# Rear_Tail_Lights_FULL.net
KiCad netlist of a schematic drawn in Altium Designer
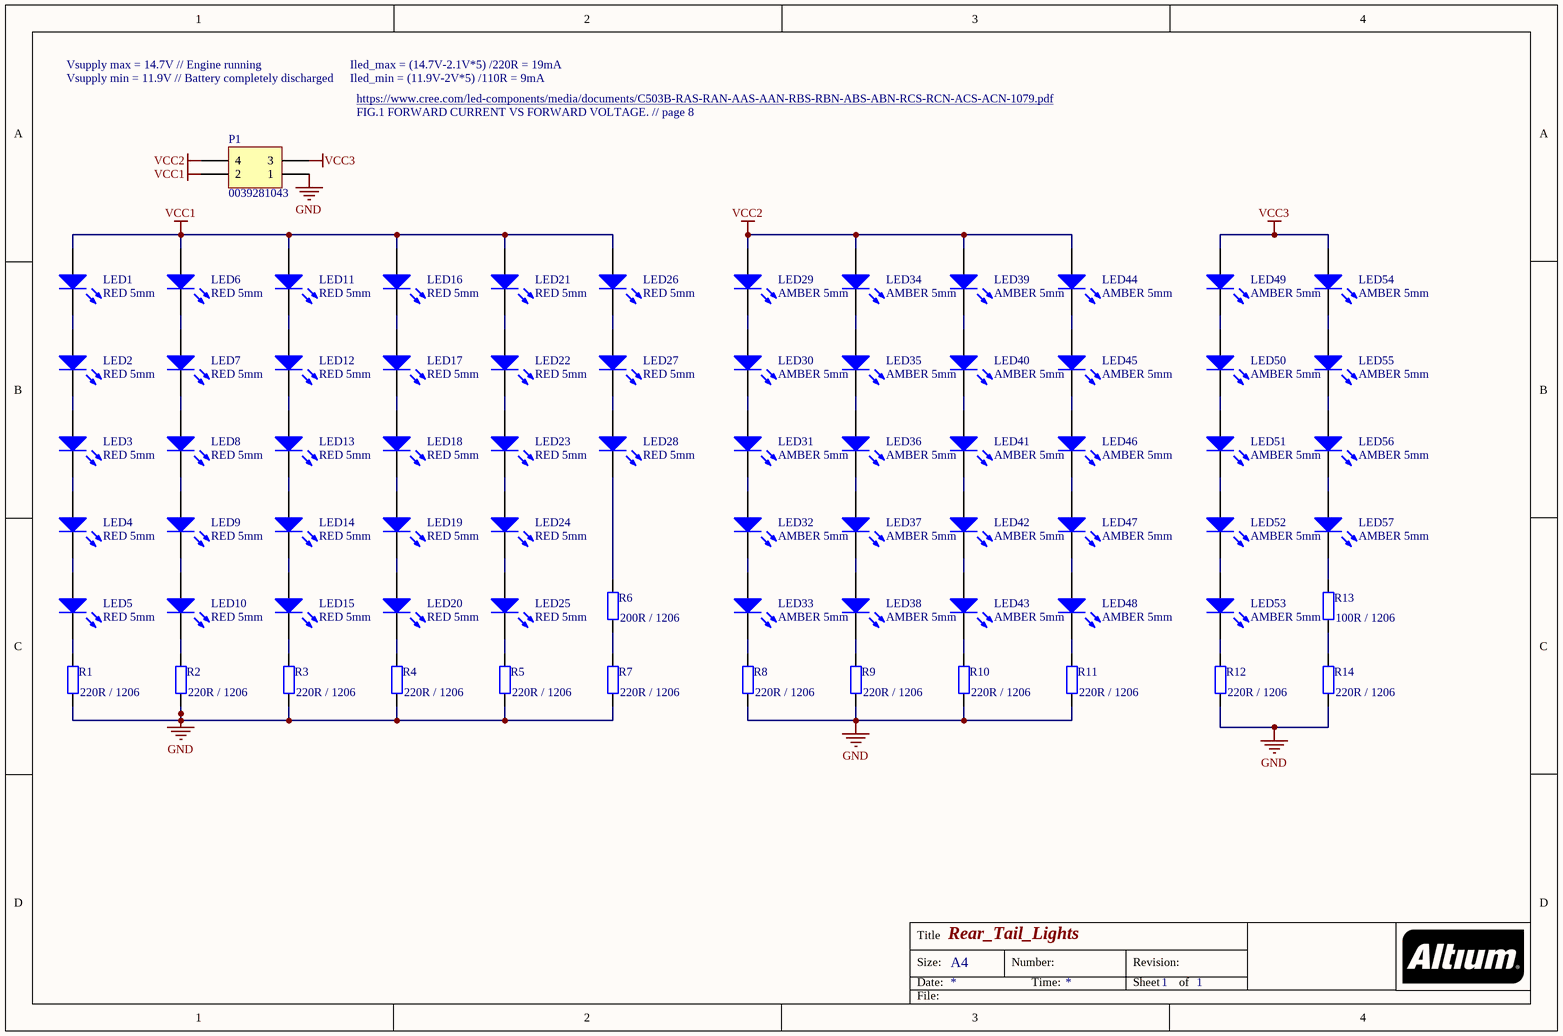
[diagram p0: Rear_Tail_Lights_FULL.SchDoc]

(export (version "E")
  (design (tool "Eeschema 10.0.6"))
  (components
    (comp (ref "LED1")
      (value "RED 5mm")
      (footprint "LED_5MM_RED_1C-2A")
      (description "LED GREEN CLEAR 0603 SMD")
      (fields (field (name "MANUFACTURER") "Lite-On Inc.") (field (name "PUBLISHER") "Altium Limited"))
      (libsource (lib "Miscellaneous Devices") (part "LED0"))
    )
    (comp (ref "LED2")
      (value "RED 5mm")
      (footprint "LED_5MM_RED_1C-2A")
      (description "LED GREEN CLEAR 0603 SMD")
      (fields (field (name "MANUFACTURER") "Lite-On Inc.") (field (name "PUBLISHER") "Altium Limited"))
      (libsource (lib "Miscellaneous Devices") (part "LED0"))
    )
    (comp (ref "LED3")
      (value "RED 5mm")
      (footprint "LED_5MM_RED_1C-2A")
      (description "LED GREEN CLEAR 0603 SMD")
      (fields (field (name "MANUFACTURER") "Lite-On Inc.") (field (name "PUBLISHER") "Altium Limited"))
      (libsource (lib "Miscellaneous Devices") (part "LED0"))
    )
    (comp (ref "LED4")
      (value "RED 5mm")
      (footprint "LED_5MM_RED_1C-2A")
      (description "LED GREEN CLEAR 0603 SMD")
      (fields (field (name "MANUFACTURER") "Lite-On Inc.") (field (name "PUBLISHER") "Altium Limited"))
      (libsource (lib "Miscellaneous Devices") (part "LED0"))
    )
    (comp (ref "LED5")
      (value "RED 5mm")
      (footprint "LED_5MM_RED_1C-2A")
      (description "LED GREEN CLEAR 0603 SMD")
      (fields (field (name "MANUFACTURER") "Lite-On Inc.") (field (name "PUBLISHER") "Altium Limited"))
      (libsource (lib "Miscellaneous Devices") (part "LED0"))
    )
    (comp (ref "LED6")
      (value "RED 5mm")
      (footprint "LED_5MM_RED_1C-2A")
      (description "LED GREEN CLEAR 0603 SMD")
      (fields (field (name "MANUFACTURER") "Lite-On Inc.") (field (name "PUBLISHER") "Altium Limited"))
      (libsource (lib "Miscellaneous Devices") (part "LED0"))
    )
    (comp (ref "LED7")
      (value "RED 5mm")
      (footprint "LED_5MM_RED_1C-2A")
      (description "LED GREEN CLEAR 0603 SMD")
      (fields (field (name "MANUFACTURER") "Lite-On Inc.") (field (name "PUBLISHER") "Altium Limited"))
      (libsource (lib "Miscellaneous Devices") (part "LED0"))
    )
    (comp (ref "LED8")
      (value "RED 5mm")
      (footprint "LED_5MM_RED_1C-2A")
      (description "LED GREEN CLEAR 0603 SMD")
      (fields (field (name "MANUFACTURER") "Lite-On Inc.") (field (name "PUBLISHER") "Altium Limited"))
      (libsource (lib "Miscellaneous Devices") (part "LED0"))
    )
    (comp (ref "LED9")
      (value "RED 5mm")
      (footprint "LED_5MM_RED_1C-2A")
      (description "LED GREEN CLEAR 0603 SMD")
      (fields (field (name "MANUFACTURER") "Lite-On Inc.") (field (name "PUBLISHER") "Altium Limited"))
      (libsource (lib "Miscellaneous Devices") (part "LED0"))
    )
    (comp (ref "LED10")
      (value "RED 5mm")
      (footprint "LED_5MM_RED_1C-2A")
      (description "LED GREEN CLEAR 0603 SMD")
      (fields (field (name "MANUFACTURER") "Lite-On Inc.") (field (name "PUBLISHER") "Altium Limited"))
      (libsource (lib "Miscellaneous Devices") (part "LED0"))
    )
    (comp (ref "LED11")
      (value "RED 5mm")
      (footprint "LED_5MM_RED_1C-2A")
      (description "LED GREEN CLEAR 0603 SMD")
      (fields (field (name "MANUFACTURER") "Lite-On Inc.") (field (name "PUBLISHER") "Altium Limited"))
      (libsource (lib "Miscellaneous Devices") (part "LED0"))
    )
    (comp (ref "LED12")
      (value "RED 5mm")
      (footprint "LED_5MM_RED_1C-2A")
      (description "LED GREEN CLEAR 0603 SMD")
      (fields (field (name "MANUFACTURER") "Lite-On Inc.") (field (name "PUBLISHER") "Altium Limited"))
      (libsource (lib "Miscellaneous Devices") (part "LED0"))
    )
    (comp (ref "LED13")
      (value "RED 5mm")
      (footprint "LED_5MM_RED_1C-2A")
      (description "LED GREEN CLEAR 0603 SMD")
      (fields (field (name "MANUFACTURER") "Lite-On Inc.") (field (name "PUBLISHER") "Altium Limited"))
      (libsource (lib "Miscellaneous Devices") (part "LED0"))
    )
    (comp (ref "LED14")
      (value "RED 5mm")
      (footprint "LED_5MM_RED_1C-2A")
      (description "LED GREEN CLEAR 0603 SMD")
      (fields (field (name "MANUFACTURER") "Lite-On Inc.") (field (name "PUBLISHER") "Altium Limited"))
      (libsource (lib "Miscellaneous Devices") (part "LED0"))
    )
    (comp (ref "LED15")
      (value "RED 5mm")
      (footprint "LED_5MM_RED_1C-2A")
      (description "LED GREEN CLEAR 0603 SMD")
      (fields (field (name "MANUFACTURER") "Lite-On Inc.") (field (name "PUBLISHER") "Altium Limited"))
      (libsource (lib "Miscellaneous Devices") (part "LED0"))
    )
    (comp (ref "LED16")
      (value "RED 5mm")
      (footprint "LED_5MM_RED_1C-2A")
      (description "LED GREEN CLEAR 0603 SMD")
      (fields (field (name "MANUFACTURER") "Lite-On Inc.") (field (name "PUBLISHER") "Altium Limited"))
      (libsource (lib "Miscellaneous Devices") (part "LED0"))
    )
    (comp (ref "LED17")
      (value "RED 5mm")
      (footprint "LED_5MM_RED_1C-2A")
      (description "LED GREEN CLEAR 0603 SMD")
      (fields (field (name "MANUFACTURER") "Lite-On Inc.") (field (name "PUBLISHER") "Altium Limited"))
      (libsource (lib "Miscellaneous Devices") (part "LED0"))
    )
    (comp (ref "LED18")
      (value "RED 5mm")
      (footprint "LED_5MM_RED_1C-2A")
      (description "LED GREEN CLEAR 0603 SMD")
      (fields (field (name "MANUFACTURER") "Lite-On Inc.") (field (name "PUBLISHER") "Altium Limited"))
      (libsource (lib "Miscellaneous Devices") (part "LED0"))
    )
    (comp (ref "LED19")
      (value "RED 5mm")
      (footprint "LED_5MM_RED_1C-2A")
      (description "LED GREEN CLEAR 0603 SMD")
      (fields (field (name "MANUFACTURER") "Lite-On Inc.") (field (name "PUBLISHER") "Altium Limited"))
      (libsource (lib "Miscellaneous Devices") (part "LED0"))
    )
    (comp (ref "LED20")
      (value "RED 5mm")
      (footprint "LED_5MM_RED_1C-2A")
      (description "LED GREEN CLEAR 0603 SMD")
      (fields (field (name "MANUFACTURER") "Lite-On Inc.") (field (name "PUBLISHER") "Altium Limited"))
      (libsource (lib "Miscellaneous Devices") (part "LED0"))
    )
    (comp (ref "LED21")
      (value "RED 5mm")
      (footprint "LED_5MM_RED_1C-2A")
      (description "LED GREEN CLEAR 0603 SMD")
      (fields (field (name "MANUFACTURER") "Lite-On Inc.") (field (name "PUBLISHER") "Altium Limited"))
      (libsource (lib "Miscellaneous Devices") (part "LED0"))
    )
    (comp (ref "LED22")
      (value "RED 5mm")
      (footprint "LED_5MM_RED_1C-2A")
      (description "LED GREEN CLEAR 0603 SMD")
      (fields (field (name "MANUFACTURER") "Lite-On Inc.") (field (name "PUBLISHER") "Altium Limited"))
      (libsource (lib "Miscellaneous Devices") (part "LED0"))
    )
    (comp (ref "LED23")
      (value "RED 5mm")
      (footprint "LED_5MM_RED_1C-2A")
      (description "LED GREEN CLEAR 0603 SMD")
      (fields (field (name "MANUFACTURER") "Lite-On Inc.") (field (name "PUBLISHER") "Altium Limited"))
      (libsource (lib "Miscellaneous Devices") (part "LED0"))
    )
    (comp (ref "LED24")
      (value "RED 5mm")
      (footprint "LED_5MM_RED_1C-2A")
      (description "LED GREEN CLEAR 0603 SMD")
      (fields (field (name "MANUFACTURER") "Lite-On Inc.") (field (name "PUBLISHER") "Altium Limited"))
      (libsource (lib "Miscellaneous Devices") (part "LED0"))
    )
    (comp (ref "LED25")
      (value "RED 5mm")
      (footprint "LED_5MM_RED_1C-2A")
      (description "LED GREEN CLEAR 0603 SMD")
      (fields (field (name "MANUFACTURER") "Lite-On Inc.") (field (name "PUBLISHER") "Altium Limited"))
      (libsource (lib "Miscellaneous Devices") (part "LED0"))
    )
    (comp (ref "LED26")
      (value "RED 5mm")
      (footprint "LED_5MM_RED_1C-2A")
      (description "LED GREEN CLEAR 0603 SMD")
      (fields (field (name "MANUFACTURER") "Lite-On Inc.") (field (name "PUBLISHER") "Altium Limited"))
      (libsource (lib "Miscellaneous Devices") (part "LED0"))
    )
    (comp (ref "LED27")
      (value "RED 5mm")
      (footprint "LED_5MM_RED_1C-2A")
      (description "LED GREEN CLEAR 0603 SMD")
      (fields (field (name "MANUFACTURER") "Lite-On Inc.") (field (name "PUBLISHER") "Altium Limited"))
      (libsource (lib "Miscellaneous Devices") (part "LED0"))
    )
    (comp (ref "LED28")
      (value "RED 5mm")
      (footprint "LED_5MM_RED_1C-2A")
      (description "LED GREEN CLEAR 0603 SMD")
      (fields (field (name "MANUFACTURER") "Lite-On Inc.") (field (name "PUBLISHER") "Altium Limited"))
      (libsource (lib "Miscellaneous Devices") (part "LED0"))
    )
    (comp (ref "LED29")
      (value "AMBER 5mm")
      (footprint "LED_5MM_YELLOW_1C-2A")
      (description "LED GREEN CLEAR 0603 SMD")
      (fields (field (name "MANUFACTURER") "Lite-On Inc.") (field (name "PUBLISHER") "Altium Limited"))
      (libsource (lib "Miscellaneous Devices") (part "LED0"))
    )
    (comp (ref "LED30")
      (value "AMBER 5mm")
      (footprint "LED_5MM_YELLOW_1C-2A")
      (description "LED GREEN CLEAR 0603 SMD")
      (fields (field (name "MANUFACTURER") "Lite-On Inc.") (field (name "PUBLISHER") "Altium Limited"))
      (libsource (lib "Miscellaneous Devices") (part "LED0"))
    )
    (comp (ref "LED31")
      (value "AMBER 5mm")
      (footprint "LED_5MM_YELLOW_1C-2A")
      (description "LED GREEN CLEAR 0603 SMD")
      (fields (field (name "MANUFACTURER") "Lite-On Inc.") (field (name "PUBLISHER") "Altium Limited"))
      (libsource (lib "Miscellaneous Devices") (part "LED0"))
    )
    (comp (ref "LED32")
      (value "AMBER 5mm")
      (footprint "LED_5MM_YELLOW_1C-2A")
      (description "LED GREEN CLEAR 0603 SMD")
      (fields (field (name "MANUFACTURER") "Lite-On Inc.") (field (name "PUBLISHER") "Altium Limited"))
      (libsource (lib "Miscellaneous Devices") (part "LED0"))
    )
    (comp (ref "LED33")
      (value "AMBER 5mm")
      (footprint "LED_5MM_YELLOW_1C-2A")
      (description "LED GREEN CLEAR 0603 SMD")
      (fields (field (name "MANUFACTURER") "Lite-On Inc.") (field (name "PUBLISHER") "Altium Limited"))
      (libsource (lib "Miscellaneous Devices") (part "LED0"))
    )
    (comp (ref "LED34")
      (value "AMBER 5mm")
      (footprint "LED_5MM_YELLOW_1C-2A")
      (description "LED GREEN CLEAR 0603 SMD")
      (fields (field (name "MANUFACTURER") "Lite-On Inc.") (field (name "PUBLISHER") "Altium Limited"))
      (libsource (lib "Miscellaneous Devices") (part "LED0"))
    )
    (comp (ref "LED35")
      (value "AMBER 5mm")
      (footprint "LED_5MM_YELLOW_1C-2A")
      (description "LED GREEN CLEAR 0603 SMD")
      (fields (field (name "MANUFACTURER") "Lite-On Inc.") (field (name "PUBLISHER") "Altium Limited"))
      (libsource (lib "Miscellaneous Devices") (part "LED0"))
    )
    (comp (ref "LED36")
      (value "AMBER 5mm")
      (footprint "LED_5MM_YELLOW_1C-2A")
      (description "LED GREEN CLEAR 0603 SMD")
      (fields (field (name "MANUFACTURER") "Lite-On Inc.") (field (name "PUBLISHER") "Altium Limited"))
      (libsource (lib "Miscellaneous Devices") (part "LED0"))
    )
    (comp (ref "LED37")
      (value "AMBER 5mm")
      (footprint "LED_5MM_YELLOW_1C-2A")
      (description "LED GREEN CLEAR 0603 SMD")
      (fields (field (name "MANUFACTURER") "Lite-On Inc.") (field (name "PUBLISHER") "Altium Limited"))
      (libsource (lib "Miscellaneous Devices") (part "LED0"))
    )
    (comp (ref "LED38")
      (value "AMBER 5mm")
      (footprint "LED_5MM_YELLOW_1C-2A")
      (description "LED GREEN CLEAR 0603 SMD")
      (fields (field (name "MANUFACTURER") "Lite-On Inc.") (field (name "PUBLISHER") "Altium Limited"))
      (libsource (lib "Miscellaneous Devices") (part "LED0"))
    )
    (comp (ref "LED39")
      (value "AMBER 5mm")
      (footprint "LED_5MM_YELLOW_1C-2A")
      (description "LED GREEN CLEAR 0603 SMD")
      (fields (field (name "MANUFACTURER") "Lite-On Inc.") (field (name "PUBLISHER") "Altium Limited"))
      (libsource (lib "Miscellaneous Devices") (part "LED0"))
    )
    (comp (ref "LED40")
      (value "AMBER 5mm")
      (footprint "LED_5MM_YELLOW_1C-2A")
      (description "LED GREEN CLEAR 0603 SMD")
      (fields (field (name "MANUFACTURER") "Lite-On Inc.") (field (name "PUBLISHER") "Altium Limited"))
      (libsource (lib "Miscellaneous Devices") (part "LED0"))
    )
    (comp (ref "LED41")
      (value "AMBER 5mm")
      (footprint "LED_5MM_YELLOW_1C-2A")
      (description "LED GREEN CLEAR 0603 SMD")
      (fields (field (name "MANUFACTURER") "Lite-On Inc.") (field (name "PUBLISHER") "Altium Limited"))
      (libsource (lib "Miscellaneous Devices") (part "LED0"))
    )
    (comp (ref "LED42")
      (value "AMBER 5mm")
      (footprint "LED_5MM_YELLOW_1C-2A")
      (description "LED GREEN CLEAR 0603 SMD")
      (fields (field (name "MANUFACTURER") "Lite-On Inc.") (field (name "PUBLISHER") "Altium Limited"))
      (libsource (lib "Miscellaneous Devices") (part "LED0"))
    )
    (comp (ref "LED43")
      (value "AMBER 5mm")
      (footprint "LED_5MM_YELLOW_1C-2A")
      (description "LED GREEN CLEAR 0603 SMD")
      (fields (field (name "MANUFACTURER") "Lite-On Inc.") (field (name "PUBLISHER") "Altium Limited"))
      (libsource (lib "Miscellaneous Devices") (part "LED0"))
    )
    (comp (ref "LED44")
      (value "AMBER 5mm")
      (footprint "LED_5MM_YELLOW_1C-2A")
      (description "LED GREEN CLEAR 0603 SMD")
      (fields (field (name "MANUFACTURER") "Lite-On Inc.") (field (name "PUBLISHER") "Altium Limited"))
      (libsource (lib "Miscellaneous Devices") (part "LED0"))
    )
    (comp (ref "LED45")
      (value "AMBER 5mm")
      (footprint "LED_5MM_YELLOW_1C-2A")
      (description "LED GREEN CLEAR 0603 SMD")
      (fields (field (name "MANUFACTURER") "Lite-On Inc.") (field (name "PUBLISHER") "Altium Limited"))
      (libsource (lib "Miscellaneous Devices") (part "LED0"))
    )
    (comp (ref "LED46")
      (value "AMBER 5mm")
      (footprint "LED_5MM_YELLOW_1C-2A")
      (description "LED GREEN CLEAR 0603 SMD")
      (fields (field (name "MANUFACTURER") "Lite-On Inc.") (field (name "PUBLISHER") "Altium Limited"))
      (libsource (lib "Miscellaneous Devices") (part "LED0"))
    )
    (comp (ref "LED47")
      (value "AMBER 5mm")
      (footprint "LED_5MM_YELLOW_1C-2A")
      (description "LED GREEN CLEAR 0603 SMD")
      (fields (field (name "MANUFACTURER") "Lite-On Inc.") (field (name "PUBLISHER") "Altium Limited"))
      (libsource (lib "Miscellaneous Devices") (part "LED0"))
    )
    (comp (ref "LED48")
      (value "AMBER 5mm")
      (footprint "LED_5MM_YELLOW_1C-2A")
      (description "LED GREEN CLEAR 0603 SMD")
      (fields (field (name "MANUFACTURER") "Lite-On Inc.") (field (name "PUBLISHER") "Altium Limited"))
      (libsource (lib "Miscellaneous Devices") (part "LED0"))
    )
    (comp (ref "LED49")
      (value "AMBER 5mm")
      (footprint "LED_5MM_YELLOW_1C-2A")
      (description "LED GREEN CLEAR 0603 SMD")
      (fields (field (name "MANUFACTURER") "Lite-On Inc.") (field (name "PUBLISHER") "Altium Limited"))
      (libsource (lib "Miscellaneous Devices") (part "LED0"))
    )
    (comp (ref "LED50")
      (value "AMBER 5mm")
      (footprint "LED_5MM_YELLOW_1C-2A")
      (description "LED GREEN CLEAR 0603 SMD")
      (fields (field (name "MANUFACTURER") "Lite-On Inc.") (field (name "PUBLISHER") "Altium Limited"))
      (libsource (lib "Miscellaneous Devices") (part "LED0"))
    )
    (comp (ref "LED51")
      (value "AMBER 5mm")
      (footprint "LED_5MM_YELLOW_1C-2A")
      (description "LED GREEN CLEAR 0603 SMD")
      (fields (field (name "MANUFACTURER") "Lite-On Inc.") (field (name "PUBLISHER") "Altium Limited"))
      (libsource (lib "Miscellaneous Devices") (part "LED0"))
    )
    (comp (ref "LED52")
      (value "AMBER 5mm")
      (footprint "LED_5MM_YELLOW_1C-2A")
      (description "LED GREEN CLEAR 0603 SMD")
      (fields (field (name "MANUFACTURER") "Lite-On Inc.") (field (name "PUBLISHER") "Altium Limited"))
      (libsource (lib "Miscellaneous Devices") (part "LED0"))
    )
    (comp (ref "LED53")
      (value "AMBER 5mm")
      (footprint "LED_5MM_YELLOW_1C-2A")
      (description "LED GREEN CLEAR 0603 SMD")
      (fields (field (name "MANUFACTURER") "Lite-On Inc.") (field (name "PUBLISHER") "Altium Limited"))
      (libsource (lib "Miscellaneous Devices") (part "LED0"))
    )
    (comp (ref "LED54")
      (value "AMBER 5mm")
      (footprint "LED_5MM_YELLOW_1C-2A")
      (description "LED GREEN CLEAR 0603 SMD")
      (fields (field (name "MANUFACTURER") "Lite-On Inc.") (field (name "PUBLISHER") "Altium Limited"))
      (libsource (lib "Miscellaneous Devices") (part "LED0"))
    )
    (comp (ref "LED55")
      (value "AMBER 5mm")
      (footprint "LED_5MM_YELLOW_1C-2A")
      (description "LED GREEN CLEAR 0603 SMD")
      (fields (field (name "MANUFACTURER") "Lite-On Inc.") (field (name "PUBLISHER") "Altium Limited"))
      (libsource (lib "Miscellaneous Devices") (part "LED0"))
    )
    (comp (ref "LED56")
      (value "AMBER 5mm")
      (footprint "LED_5MM_YELLOW_1C-2A")
      (description "LED GREEN CLEAR 0603 SMD")
      (fields (field (name "MANUFACTURER") "Lite-On Inc.") (field (name "PUBLISHER") "Altium Limited"))
      (libsource (lib "Miscellaneous Devices") (part "LED0"))
    )
    (comp (ref "LED57")
      (value "AMBER 5mm")
      (footprint "LED_5MM_YELLOW_1C-2A")
      (description "LED GREEN CLEAR 0603 SMD")
      (fields (field (name "MANUFACTURER") "Lite-On Inc.") (field (name "PUBLISHER") "Altium Limited"))
      (libsource (lib "Miscellaneous Devices") (part "LED0"))
    )
    (comp (ref "P1")
      (value "0039281043")
      (footprint "0039281043")
      (description "Header, 2-Pin, Dual row")
      (fields (field (name "PUBLISHER") "Altium Limited"))
      (libsource (lib "Miscellaneous Connectors") (part "Header 2X2"))
    )
    (comp (ref "R1")
      (value "220R / 1206")
      (footprint "RESC3216X70N")
      (description "Resistor")
      (libsource (lib "Passives") (part "R_EU"))
    )
    (comp (ref "R2")
      (value "220R / 1206")
      (footprint "RESC3216X70N")
      (description "Resistor")
      (libsource (lib "Passives") (part "R_EU"))
    )
    (comp (ref "R3")
      (value "220R / 1206")
      (footprint "RESC3216X70N")
      (description "Resistor")
      (libsource (lib "Passives") (part "R_EU"))
    )
    (comp (ref "R4")
      (value "220R / 1206")
      (footprint "RESC3216X70N")
      (description "Resistor")
      (libsource (lib "Passives") (part "R_EU"))
    )
    (comp (ref "R5")
      (value "220R / 1206")
      (footprint "RESC3216X70N")
      (description "Resistor")
      (libsource (lib "Passives") (part "R_EU"))
    )
    (comp (ref "R6")
      (value "200R / 1206")
      (footprint "RESC3216X70N")
      (description "Resistor")
      (libsource (lib "Passives") (part "R_EU"))
    )
    (comp (ref "R7")
      (value "220R / 1206")
      (footprint "RESC3216X70N")
      (description "Resistor")
      (libsource (lib "Passives") (part "R_EU"))
    )
    (comp (ref "R8")
      (value "220R / 1206")
      (footprint "RESC3216X70N")
      (description "Resistor")
      (libsource (lib "Passives") (part "R_EU"))
    )
    (comp (ref "R9")
      (value "220R / 1206")
      (footprint "RESC3216X70N")
      (description "Resistor")
      (libsource (lib "Passives") (part "R_EU"))
    )
    (comp (ref "R10")
      (value "220R / 1206")
      (footprint "RESC3216X70N")
      (description "Resistor")
      (libsource (lib "Passives") (part "R_EU"))
    )
    (comp (ref "R11")
      (value "220R / 1206")
      (footprint "RESC3216X70N")
      (description "Resistor")
      (libsource (lib "Passives") (part "R_EU"))
    )
    (comp (ref "R12")
      (value "220R / 1206")
      (footprint "RESC3216X70N")
      (description "Resistor")
      (libsource (lib "Passives") (part "R_EU"))
    )
    (comp (ref "R13")
      (value "100R / 1206")
      (footprint "RESC3216X70N")
      (description "Resistor")
      (libsource (lib "Passives") (part "R_EU"))
    )
    (comp (ref "R14")
      (value "220R / 1206")
      (footprint "RESC3216X70N")
      (description "Resistor")
      (libsource (lib "Passives") (part "R_EU"))
    )
  )
  (nets
    (net (code "1") (name "GND") (class "Default")
      (node (ref "P1") (pin "1") (pinfunction "1_1") (pintype "passive"))
      (node (ref "R1") (pin "2") (pinfunction "2_2") (pintype "passive"))
      (node (ref "R10") (pin "2") (pinfunction "2_2") (pintype "passive"))
      (node (ref "R11") (pin "2") (pinfunction "2_2") (pintype "passive"))
      (node (ref "R12") (pin "2") (pinfunction "2_2") (pintype "passive"))
      (node (ref "R14") (pin "2") (pinfunction "2_2") (pintype "passive"))
      (node (ref "R2") (pin "2") (pinfunction "2_2") (pintype "passive"))
      (node (ref "R3") (pin "2") (pinfunction "2_2") (pintype "passive"))
      (node (ref "R4") (pin "2") (pinfunction "2_2") (pintype "passive"))
      (node (ref "R5") (pin "2") (pinfunction "2_2") (pintype "passive"))
      (node (ref "R7") (pin "2") (pinfunction "2_2") (pintype "passive"))
      (node (ref "R8") (pin "2") (pinfunction "2_2") (pintype "passive"))
      (node (ref "R9") (pin "2") (pinfunction "2_2") (pintype "passive"))
    )
    (net (code "2") (name "Net-(LED1-K)") (class "Default")
      (node (ref "LED1") (pin "1") (pinfunction "K_1") (pintype "passive"))
      (node (ref "LED2") (pin "2") (pinfunction "A_2") (pintype "passive"))
    )
    (net (code "3") (name "Net-(LED2-K)") (class "Default")
      (node (ref "LED2") (pin "1") (pinfunction "K_1") (pintype "passive"))
      (node (ref "LED3") (pin "2") (pinfunction "A_2") (pintype "passive"))
    )
    (net (code "4") (name "Net-(LED3-K)") (class "Default")
      (node (ref "LED3") (pin "1") (pinfunction "K_1") (pintype "passive"))
      (node (ref "LED4") (pin "2") (pinfunction "A_2") (pintype "passive"))
    )
    (net (code "5") (name "Net-(LED4-K)") (class "Default")
      (node (ref "LED4") (pin "1") (pinfunction "K_1") (pintype "passive"))
      (node (ref "LED5") (pin "2") (pinfunction "A_2") (pintype "passive"))
    )
    (net (code "6") (name "Net-(LED5-K)") (class "Default")
      (node (ref "LED5") (pin "1") (pinfunction "K_1") (pintype "passive"))
      (node (ref "R1") (pin "1") (pinfunction "1_1") (pintype "passive"))
    )
    (net (code "7") (name "Net-(LED6-K)") (class "Default")
      (node (ref "LED6") (pin "1") (pinfunction "K_1") (pintype "passive"))
      (node (ref "LED7") (pin "2") (pinfunction "A_2") (pintype "passive"))
    )
    (net (code "8") (name "Net-(LED7-K)") (class "Default")
      (node (ref "LED7") (pin "1") (pinfunction "K_1") (pintype "passive"))
      (node (ref "LED8") (pin "2") (pinfunction "A_2") (pintype "passive"))
    )
    (net (code "9") (name "Net-(LED8-K)") (class "Default")
      (node (ref "LED8") (pin "1") (pinfunction "K_1") (pintype "passive"))
      (node (ref "LED9") (pin "2") (pinfunction "A_2") (pintype "passive"))
    )
    (net (code "10") (name "Net-(LED10-A)") (class "Default")
      (node (ref "LED10") (pin "2") (pinfunction "A_2") (pintype "passive"))
      (node (ref "LED9") (pin "1") (pinfunction "K_1") (pintype "passive"))
    )
    (net (code "11") (name "Net-(LED10-K)") (class "Default")
      (node (ref "LED10") (pin "1") (pinfunction "K_1") (pintype "passive"))
      (node (ref "R2") (pin "1") (pinfunction "1_1") (pintype "passive"))
    )
    (net (code "12") (name "Net-(LED11-K)") (class "Default")
      (node (ref "LED11") (pin "1") (pinfunction "K_1") (pintype "passive"))
      (node (ref "LED12") (pin "2") (pinfunction "A_2") (pintype "passive"))
    )
    (net (code "13") (name "Net-(LED12-K)") (class "Default")
      (node (ref "LED12") (pin "1") (pinfunction "K_1") (pintype "passive"))
      (node (ref "LED13") (pin "2") (pinfunction "A_2") (pintype "passive"))
    )
    (net (code "14") (name "Net-(LED13-K)") (class "Default")
      (node (ref "LED13") (pin "1") (pinfunction "K_1") (pintype "passive"))
      (node (ref "LED14") (pin "2") (pinfunction "A_2") (pintype "passive"))
    )
    (net (code "15") (name "Net-(LED14-K)") (class "Default")
      (node (ref "LED14") (pin "1") (pinfunction "K_1") (pintype "passive"))
      (node (ref "LED15") (pin "2") (pinfunction "A_2") (pintype "passive"))
    )
    (net (code "16") (name "Net-(LED15-K)") (class "Default")
      (node (ref "LED15") (pin "1") (pinfunction "K_1") (pintype "passive"))
      (node (ref "R3") (pin "1") (pinfunction "1_1") (pintype "passive"))
    )
    (net (code "17") (name "Net-(LED16-K)") (class "Default")
      (node (ref "LED16") (pin "1") (pinfunction "K_1") (pintype "passive"))
      (node (ref "LED17") (pin "2") (pinfunction "A_2") (pintype "passive"))
    )
    (net (code "18") (name "Net-(LED17-K)") (class "Default")
      (node (ref "LED17") (pin "1") (pinfunction "K_1") (pintype "passive"))
      (node (ref "LED18") (pin "2") (pinfunction "A_2") (pintype "passive"))
    )
    (net (code "19") (name "Net-(LED18-K)") (class "Default")
      (node (ref "LED18") (pin "1") (pinfunction "K_1") (pintype "passive"))
      (node (ref "LED19") (pin "2") (pinfunction "A_2") (pintype "passive"))
    )
    (net (code "20") (name "Net-(LED19-K)") (class "Default")
      (node (ref "LED19") (pin "1") (pinfunction "K_1") (pintype "passive"))
      (node (ref "LED20") (pin "2") (pinfunction "A_2") (pintype "passive"))
    )
    (net (code "21") (name "Net-(LED20-K)") (class "Default")
      (node (ref "LED20") (pin "1") (pinfunction "K_1") (pintype "passive"))
      (node (ref "R4") (pin "1") (pinfunction "1_1") (pintype "passive"))
    )
    (net (code "22") (name "Net-(LED21-K)") (class "Default")
      (node (ref "LED21") (pin "1") (pinfunction "K_1") (pintype "passive"))
      (node (ref "LED22") (pin "2") (pinfunction "A_2") (pintype "passive"))
    )
    (net (code "23") (name "Net-(LED22-K)") (class "Default")
      (node (ref "LED22") (pin "1") (pinfunction "K_1") (pintype "passive"))
      (node (ref "LED23") (pin "2") (pinfunction "A_2") (pintype "passive"))
    )
    (net (code "24") (name "Net-(LED23-K)") (class "Default")
      (node (ref "LED23") (pin "1") (pinfunction "K_1") (pintype "passive"))
      (node (ref "LED24") (pin "2") (pinfunction "A_2") (pintype "passive"))
    )
    (net (code "25") (name "Net-(LED24-K)") (class "Default")
      (node (ref "LED24") (pin "1") (pinfunction "K_1") (pintype "passive"))
      (node (ref "LED25") (pin "2") (pinfunction "A_2") (pintype "passive"))
    )
    (net (code "26") (name "Net-(LED25-K)") (class "Default")
      (node (ref "LED25") (pin "1") (pinfunction "K_1") (pintype "passive"))
      (node (ref "R5") (pin "1") (pinfunction "1_1") (pintype "passive"))
    )
    (net (code "27") (name "Net-(LED26-K)") (class "Default")
      (node (ref "LED26") (pin "1") (pinfunction "K_1") (pintype "passive"))
      (node (ref "LED27") (pin "2") (pinfunction "A_2") (pintype "passive"))
    )
    (net (code "28") (name "Net-(LED27-K)") (class "Default")
      (node (ref "LED27") (pin "1") (pinfunction "K_1") (pintype "passive"))
      (node (ref "LED28") (pin "2") (pinfunction "A_2") (pintype "passive"))
    )
    (net (code "29") (name "Net-(LED28-K)") (class "Default")
      (node (ref "LED28") (pin "1") (pinfunction "K_1") (pintype "passive"))
      (node (ref "R6") (pin "1") (pinfunction "1_1") (pintype "passive"))
    )
    (net (code "30") (name "Net-(LED29-K)") (class "Default")
      (node (ref "LED29") (pin "1") (pinfunction "K_1") (pintype "passive"))
      (node (ref "LED30") (pin "2") (pinfunction "A_2") (pintype "passive"))
    )
    (net (code "31") (name "Net-(LED30-K)") (class "Default")
      (node (ref "LED30") (pin "1") (pinfunction "K_1") (pintype "passive"))
      (node (ref "LED31") (pin "2") (pinfunction "A_2") (pintype "passive"))
    )
    (net (code "32") (name "Net-(LED31-K)") (class "Default")
      (node (ref "LED31") (pin "1") (pinfunction "K_1") (pintype "passive"))
      (node (ref "LED32") (pin "2") (pinfunction "A_2") (pintype "passive"))
    )
    (net (code "33") (name "Net-(LED32-K)") (class "Default")
      (node (ref "LED32") (pin "1") (pinfunction "K_1") (pintype "passive"))
      (node (ref "LED33") (pin "2") (pinfunction "A_2") (pintype "passive"))
    )
    (net (code "34") (name "Net-(LED33-K)") (class "Default")
      (node (ref "LED33") (pin "1") (pinfunction "K_1") (pintype "passive"))
      (node (ref "R8") (pin "1") (pinfunction "1_1") (pintype "passive"))
    )
    (net (code "35") (name "Net-(LED34-K)") (class "Default")
      (node (ref "LED34") (pin "1") (pinfunction "K_1") (pintype "passive"))
      (node (ref "LED35") (pin "2") (pinfunction "A_2") (pintype "passive"))
    )
    (net (code "36") (name "Net-(LED35-K)") (class "Default")
      (node (ref "LED35") (pin "1") (pinfunction "K_1") (pintype "passive"))
      (node (ref "LED36") (pin "2") (pinfunction "A_2") (pintype "passive"))
    )
    (net (code "37") (name "Net-(LED36-K)") (class "Default")
      (node (ref "LED36") (pin "1") (pinfunction "K_1") (pintype "passive"))
      (node (ref "LED37") (pin "2") (pinfunction "A_2") (pintype "passive"))
    )
    (net (code "38") (name "Net-(LED37-K)") (class "Default")
      (node (ref "LED37") (pin "1") (pinfunction "K_1") (pintype "passive"))
      (node (ref "LED38") (pin "2") (pinfunction "A_2") (pintype "passive"))
    )
    (net (code "39") (name "Net-(LED38-K)") (class "Default")
      (node (ref "LED38") (pin "1") (pinfunction "K_1") (pintype "passive"))
      (node (ref "R9") (pin "1") (pinfunction "1_1") (pintype "passive"))
    )
    (net (code "40") (name "Net-(LED39-K)") (class "Default")
      (node (ref "LED39") (pin "1") (pinfunction "K_1") (pintype "passive"))
      (node (ref "LED40") (pin "2") (pinfunction "A_2") (pintype "passive"))
    )
    (net (code "41") (name "Net-(LED40-K)") (class "Default")
      (node (ref "LED40") (pin "1") (pinfunction "K_1") (pintype "passive"))
      (node (ref "LED41") (pin "2") (pinfunction "A_2") (pintype "passive"))
    )
    (net (code "42") (name "Net-(LED41-K)") (class "Default")
      (node (ref "LED41") (pin "1") (pinfunction "K_1") (pintype "passive"))
      (node (ref "LED42") (pin "2") (pinfunction "A_2") (pintype "passive"))
    )
    (net (code "43") (name "Net-(LED42-K)") (class "Default")
      (node (ref "LED42") (pin "1") (pinfunction "K_1") (pintype "passive"))
      (node (ref "LED43") (pin "2") (pinfunction "A_2") (pintype "passive"))
    )
    (net (code "44") (name "Net-(LED43-K)") (class "Default")
      (node (ref "LED43") (pin "1") (pinfunction "K_1") (pintype "passive"))
      (node (ref "R10") (pin "1") (pinfunction "1_1") (pintype "passive"))
    )
    (net (code "45") (name "Net-(LED44-K)") (class "Default")
      (node (ref "LED44") (pin "1") (pinfunction "K_1") (pintype "passive"))
      (node (ref "LED45") (pin "2") (pinfunction "A_2") (pintype "passive"))
    )
    (net (code "46") (name "Net-(LED45-K)") (class "Default")
      (node (ref "LED45") (pin "1") (pinfunction "K_1") (pintype "passive"))
      (node (ref "LED46") (pin "2") (pinfunction "A_2") (pintype "passive"))
    )
    (net (code "47") (name "Net-(LED46-K)") (class "Default")
      (node (ref "LED46") (pin "1") (pinfunction "K_1") (pintype "passive"))
      (node (ref "LED47") (pin "2") (pinfunction "A_2") (pintype "passive"))
    )
    (net (code "48") (name "Net-(LED47-K)") (class "Default")
      (node (ref "LED47") (pin "1") (pinfunction "K_1") (pintype "passive"))
      (node (ref "LED48") (pin "2") (pinfunction "A_2") (pintype "passive"))
    )
    (net (code "49") (name "Net-(LED48-K)") (class "Default")
      (node (ref "LED48") (pin "1") (pinfunction "K_1") (pintype "passive"))
      (node (ref "R11") (pin "1") (pinfunction "1_1") (pintype "passive"))
    )
    (net (code "50") (name "Net-(LED49-K)") (class "Default")
      (node (ref "LED49") (pin "1") (pinfunction "K_1") (pintype "passive"))
      (node (ref "LED50") (pin "2") (pinfunction "A_2") (pintype "passive"))
    )
    (net (code "51") (name "Net-(LED50-K)") (class "Default")
      (node (ref "LED50") (pin "1") (pinfunction "K_1") (pintype "passive"))
      (node (ref "LED51") (pin "2") (pinfunction "A_2") (pintype "passive"))
    )
    (net (code "52") (name "Net-(LED51-K)") (class "Default")
      (node (ref "LED51") (pin "1") (pinfunction "K_1") (pintype "passive"))
      (node (ref "LED52") (pin "2") (pinfunction "A_2") (pintype "passive"))
    )
    (net (code "53") (name "Net-(LED52-K)") (class "Default")
      (node (ref "LED52") (pin "1") (pinfunction "K_1") (pintype "passive"))
      (node (ref "LED53") (pin "2") (pinfunction "A_2") (pintype "passive"))
    )
    (net (code "54") (name "Net-(LED53-K)") (class "Default")
      (node (ref "LED53") (pin "1") (pinfunction "K_1") (pintype "passive"))
      (node (ref "R12") (pin "1") (pinfunction "1_1") (pintype "passive"))
    )
    (net (code "55") (name "Net-(LED54-K)") (class "Default")
      (node (ref "LED54") (pin "1") (pinfunction "K_1") (pintype "passive"))
      (node (ref "LED55") (pin "2") (pinfunction "A_2") (pintype "passive"))
    )
    (net (code "56") (name "Net-(LED55-K)") (class "Default")
      (node (ref "LED55") (pin "1") (pinfunction "K_1") (pintype "passive"))
      (node (ref "LED56") (pin "2") (pinfunction "A_2") (pintype "passive"))
    )
    (net (code "57") (name "Net-(LED56-K)") (class "Default")
      (node (ref "LED56") (pin "1") (pinfunction "K_1") (pintype "passive"))
      (node (ref "LED57") (pin "2") (pinfunction "A_2") (pintype "passive"))
    )
    (net (code "58") (name "Net-(LED57-K)") (class "Default")
      (node (ref "LED57") (pin "1") (pinfunction "K_1") (pintype "passive"))
      (node (ref "R13") (pin "1") (pinfunction "1_1") (pintype "passive"))
    )
    (net (code "59") (name "Net-(R6-Pad2)") (class "Default")
      (node (ref "R6") (pin "2") (pinfunction "2_2") (pintype "passive"))
      (node (ref "R7") (pin "1") (pinfunction "1_1") (pintype "passive"))
    )
    (net (code "60") (name "Net-(R13-Pad2)") (class "Default")
      (node (ref "R13") (pin "2") (pinfunction "2_2") (pintype "passive"))
      (node (ref "R14") (pin "1") (pinfunction "1_1") (pintype "passive"))
    )
    (net (code "61") (name "VCC1") (class "Default")
      (node (ref "LED1") (pin "2") (pinfunction "A_2") (pintype "passive"))
      (node (ref "LED11") (pin "2") (pinfunction "A_2") (pintype "passive"))
      (node (ref "LED16") (pin "2") (pinfunction "A_2") (pintype "passive"))
      (node (ref "LED21") (pin "2") (pinfunction "A_2") (pintype "passive"))
      (node (ref "LED26") (pin "2") (pinfunction "A_2") (pintype "passive"))
      (node (ref "LED6") (pin "2") (pinfunction "A_2") (pintype "passive"))
      (node (ref "P1") (pin "2") (pinfunction "2_2") (pintype "passive"))
    )
    (net (code "62") (name "VCC2") (class "Default")
      (node (ref "LED29") (pin "2") (pinfunction "A_2") (pintype "passive"))
      (node (ref "LED34") (pin "2") (pinfunction "A_2") (pintype "passive"))
      (node (ref "LED39") (pin "2") (pinfunction "A_2") (pintype "passive"))
      (node (ref "LED44") (pin "2") (pinfunction "A_2") (pintype "passive"))
      (node (ref "P1") (pin "4") (pinfunction "4_4") (pintype "passive"))
    )
    (net (code "63") (name "VCC3") (class "Default")
      (node (ref "LED49") (pin "2") (pinfunction "A_2") (pintype "passive"))
      (node (ref "LED54") (pin "2") (pinfunction "A_2") (pintype "passive"))
      (node (ref "P1") (pin "3") (pinfunction "3_3") (pintype "passive"))
    )
  )
)
